# smart_tft.net
KiCad netlist of a schematic drawn in EAGLE
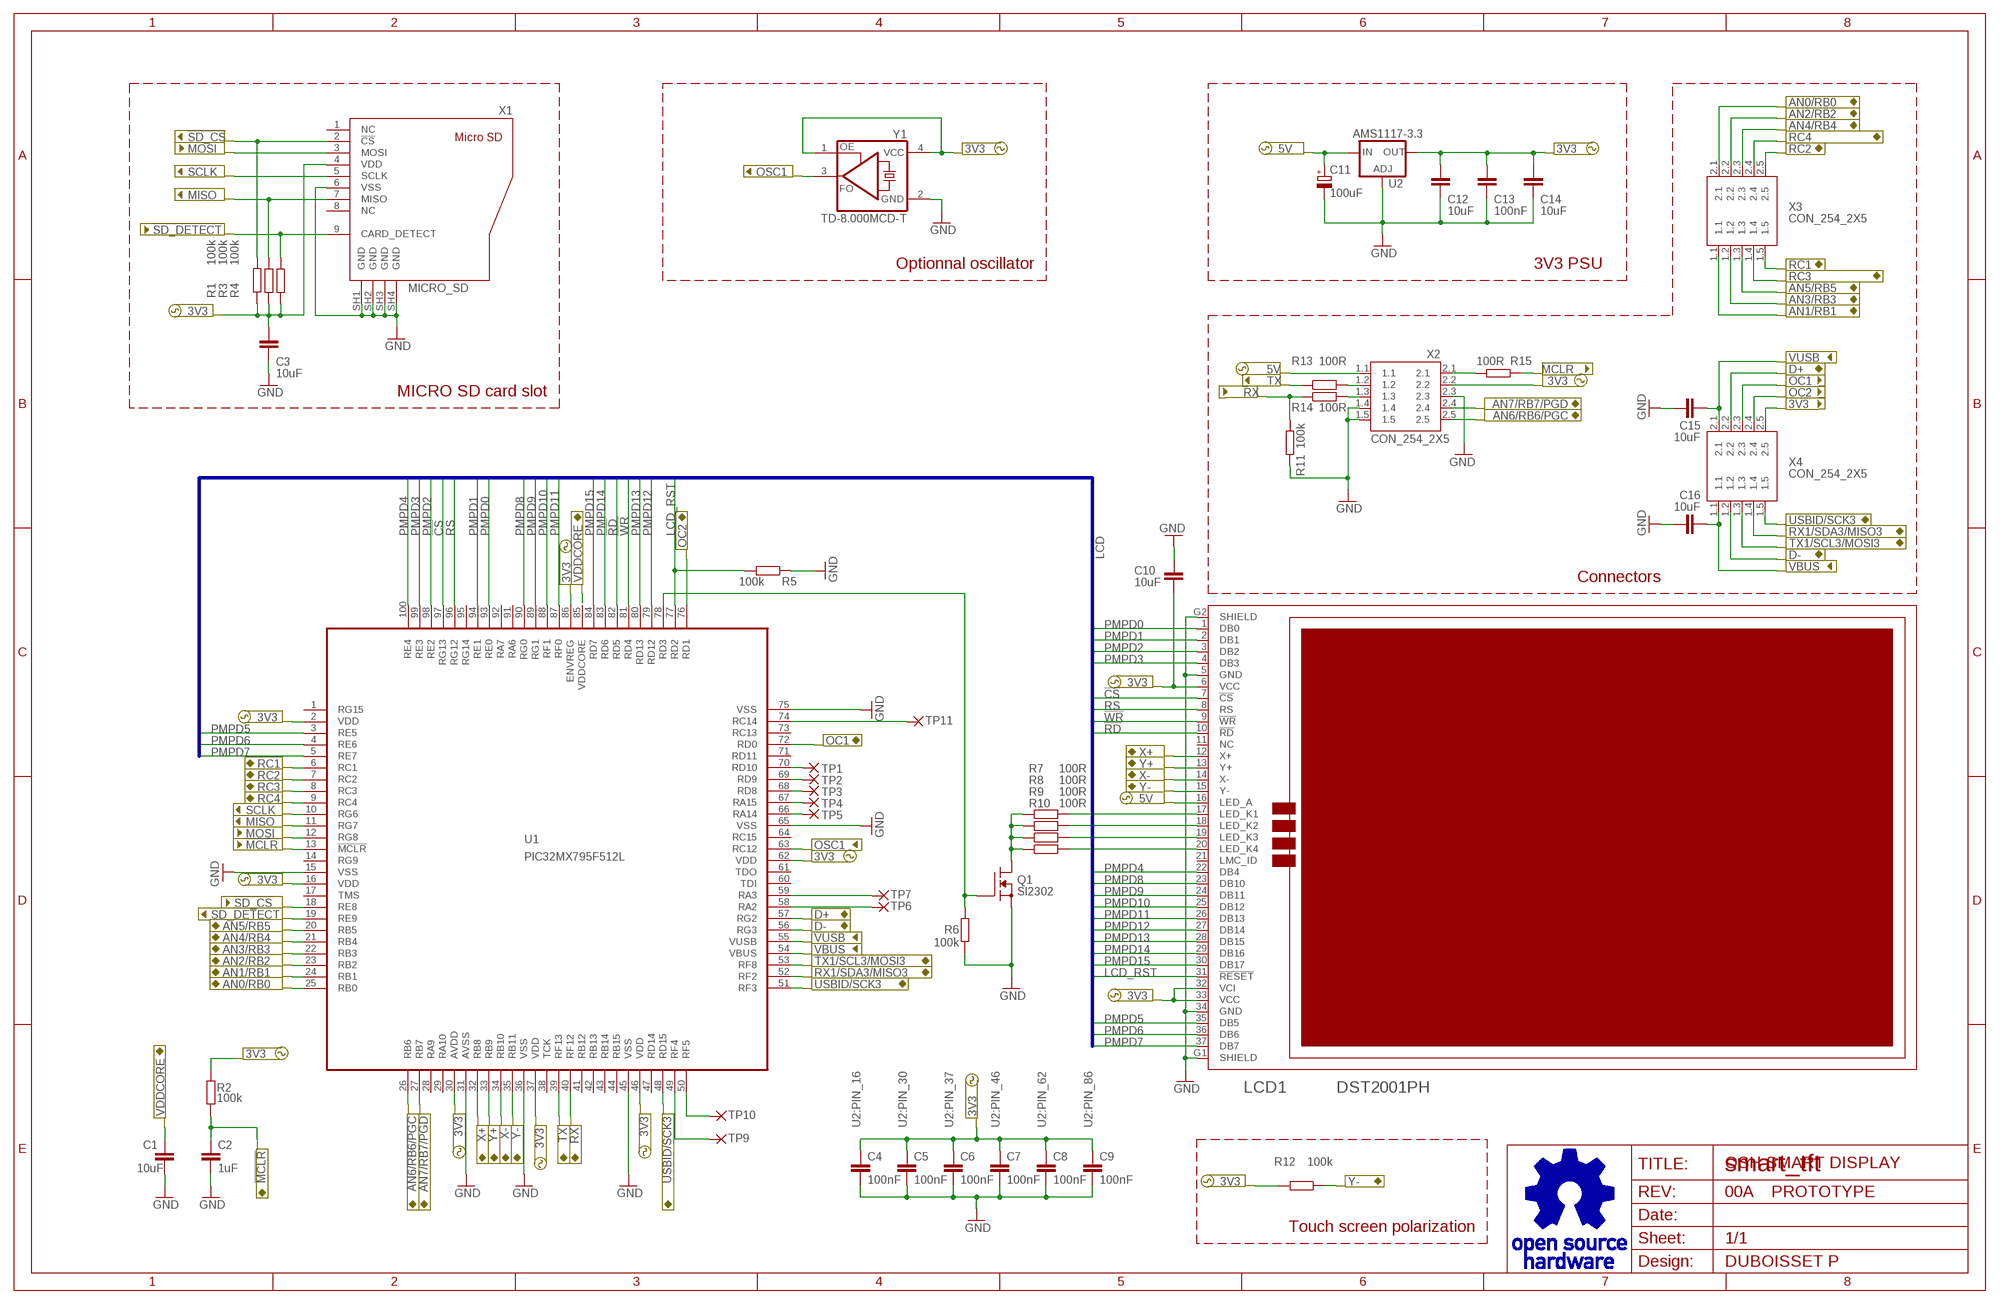
[diagram p0: schematic, sheet 1]

(export (version "E")
  (design (tool "Eeschema 10.0.6"))
  (components
    (comp (ref "C1")
      (value "10uF")
      (footprint "eagle-import:C0805")
      (libsource (lib "eagle-import") (part "C-EUC0805"))
    )
    (comp (ref "C2")
      (value "1uF")
      (footprint "eagle-import:C0603")
      (libsource (lib "eagle-import") (part "C-EUC0603"))
    )
    (comp (ref "C3")
      (value "10uF")
      (footprint "eagle-import:C0805")
      (libsource (lib "eagle-import") (part "C-EUC0805"))
    )
    (comp (ref "C4")
      (value "100nF")
      (footprint "eagle-import:C0603")
      (libsource (lib "eagle-import") (part "C-EUC0603"))
    )
    (comp (ref "C5")
      (value "100nF")
      (footprint "eagle-import:C0603")
      (libsource (lib "eagle-import") (part "C-EUC0603"))
    )
    (comp (ref "C6")
      (value "100nF")
      (footprint "eagle-import:C0603")
      (libsource (lib "eagle-import") (part "C-EUC0603"))
    )
    (comp (ref "C7")
      (value "100nF")
      (footprint "eagle-import:C0603")
      (libsource (lib "eagle-import") (part "C-EUC0603"))
    )
    (comp (ref "C8")
      (value "100nF")
      (footprint "eagle-import:C0603")
      (libsource (lib "eagle-import") (part "C-EUC0603"))
    )
    (comp (ref "C9")
      (value "100nF")
      (footprint "eagle-import:C0603")
      (libsource (lib "eagle-import") (part "C-EUC0603"))
    )
    (comp (ref "C10")
      (value "10uF")
      (footprint "eagle-import:C0805")
      (libsource (lib "eagle-import") (part "C-EUC0805"))
    )
    (comp (ref "C11")
      (value "100uF")
      (footprint "eagle-import:SMC_D")
      (libsource (lib "eagle-import") (part "CPOL-EUSMCD"))
    )
    (comp (ref "C12")
      (value "10uF")
      (footprint "eagle-import:C0805")
      (libsource (lib "eagle-import") (part "C-EUC0805"))
    )
    (comp (ref "C13")
      (value "100nF")
      (footprint "eagle-import:C0603")
      (libsource (lib "eagle-import") (part "C-EUC0603"))
    )
    (comp (ref "C14")
      (value "10uF")
      (footprint "eagle-import:C0805")
      (libsource (lib "eagle-import") (part "C-EUC0805"))
    )
    (comp (ref "C15")
      (value "10uF")
      (footprint "eagle-import:C0805")
      (libsource (lib "eagle-import") (part "C-EUC0805"))
    )
    (comp (ref "C16")
      (value "10uF")
      (footprint "eagle-import:C0805")
      (libsource (lib "eagle-import") (part "C-EUC0805"))
    )
    (comp (ref "LCD1")
      (value "DST2001PH")
      (footprint "eagle-import:DST2001PH")
      (libsource (lib "eagle-import") (part "DST2001PH"))
    )
    (comp (ref "Q1")
      (value "SI2302")
      (footprint "eagle-import:SOT23-BEC")
      (libsource (lib "eagle-import") (part "SI2302"))
    )
    (comp (ref "R1")
      (value "100k")
      (footprint "eagle-import:R0603")
      (libsource (lib "eagle-import") (part "R-EU_R0603"))
    )
    (comp (ref "R2")
      (value "100k")
      (footprint "eagle-import:R0603")
      (libsource (lib "eagle-import") (part "R-EU_R0603"))
    )
    (comp (ref "R3")
      (value "100k")
      (footprint "eagle-import:R0603")
      (libsource (lib "eagle-import") (part "R-EU_R0603"))
    )
    (comp (ref "R4")
      (value "100k")
      (footprint "eagle-import:R0603")
      (libsource (lib "eagle-import") (part "R-EU_R0603"))
    )
    (comp (ref "R5")
      (value "100k")
      (footprint "eagle-import:R0603")
      (libsource (lib "eagle-import") (part "R-EU_R0603"))
    )
    (comp (ref "R6")
      (value "100k")
      (footprint "eagle-import:R0603")
      (libsource (lib "eagle-import") (part "R-EU_R0603"))
    )
    (comp (ref "R7")
      (value "100R")
      (footprint "eagle-import:R0603")
      (libsource (lib "eagle-import") (part "R-EU_R0603"))
    )
    (comp (ref "R8")
      (value "100R")
      (footprint "eagle-import:R0603")
      (libsource (lib "eagle-import") (part "R-EU_R0603"))
    )
    (comp (ref "R9")
      (value "100R")
      (footprint "eagle-import:R0603")
      (libsource (lib "eagle-import") (part "R-EU_R0603"))
    )
    (comp (ref "R10")
      (value "100R")
      (footprint "eagle-import:R0603")
      (libsource (lib "eagle-import") (part "R-EU_R0603"))
    )
    (comp (ref "R11")
      (value "100k")
      (footprint "eagle-import:R0603")
      (libsource (lib "eagle-import") (part "R-EU_R0603"))
    )
    (comp (ref "R12")
      (value "100k")
      (footprint "eagle-import:R0603")
      (libsource (lib "eagle-import") (part "R-EU_R0603"))
    )
    (comp (ref "R13")
      (value "100R")
      (footprint "eagle-import:R0603")
      (libsource (lib "eagle-import") (part "R-EU_R0603"))
    )
    (comp (ref "R14")
      (value "100R")
      (footprint "eagle-import:R0603")
      (libsource (lib "eagle-import") (part "R-EU_R0603"))
    )
    (comp (ref "R15")
      (value "100R")
      (footprint "eagle-import:R0603")
      (libsource (lib "eagle-import") (part "R-EU_R0603"))
    )
    (comp (ref "TP1")
      (value "1.27R")
      (footprint "eagle-import:1.27R")
      (libsource (lib "eagle-import") (part "1.27R"))
    )
    (comp (ref "TP2")
      (value "1.27R")
      (footprint "eagle-import:1.27R")
      (libsource (lib "eagle-import") (part "1.27R"))
    )
    (comp (ref "TP3")
      (value "1.27R")
      (footprint "eagle-import:1.27R")
      (libsource (lib "eagle-import") (part "1.27R"))
    )
    (comp (ref "TP4")
      (value "1.27R")
      (footprint "eagle-import:1.27R")
      (libsource (lib "eagle-import") (part "1.27R"))
    )
    (comp (ref "TP5")
      (value "1.27R")
      (footprint "eagle-import:1.27R")
      (libsource (lib "eagle-import") (part "1.27R"))
    )
    (comp (ref "TP6")
      (value "1.27R")
      (footprint "eagle-import:1.27R")
      (libsource (lib "eagle-import") (part "1.27R"))
    )
    (comp (ref "TP7")
      (value "1.27R")
      (footprint "eagle-import:1.27R")
      (libsource (lib "eagle-import") (part "1.27R"))
    )
    (comp (ref "TP9")
      (value "1.27R")
      (footprint "eagle-import:1.27R")
      (libsource (lib "eagle-import") (part "1.27R"))
    )
    (comp (ref "TP10")
      (value "1.27R")
      (footprint "eagle-import:1.27R")
      (libsource (lib "eagle-import") (part "1.27R"))
    )
    (comp (ref "TP11")
      (value "1.27R")
      (footprint "eagle-import:1.27R")
      (libsource (lib "eagle-import") (part "1.27R"))
    )
    (comp (ref "U1")
      (value "PIC32MX795F512L")
      (footprint "eagle-import:TQFP100-14X14")
      (fields (field (name "MPN") "PIC24FJ256GB110-I/PF"))
      (libsource (lib "eagle-import") (part "PIC24FJ256GB110"))
    )
    (comp (ref "U2")
      (value "AMS1117-3.3")
      (footprint "eagle-import:SOT223")
      (libsource (lib "eagle-import") (part "LD117A?S33TR"))
    )
    (comp (ref "X1")
      (value "MICRO_SD")
      (footprint "eagle-import:SD_MICRO")
      (libsource (lib "eagle-import") (part "MICRO_SD"))
    )
    (comp (ref "X2")
      (value "CON_254_2X5")
      (footprint "eagle-import:2X5_CMS")
      (libsource (lib "eagle-import") (part "CON_254_2X5"))
    )
    (comp (ref "X3")
      (value "CON_254_2X5")
      (footprint "eagle-import:2X5_CMS")
      (libsource (lib "eagle-import") (part "CON_254_2X5"))
    )
    (comp (ref "X4")
      (value "CON_254_2X5")
      (footprint "eagle-import:2X5_CMS")
      (libsource (lib "eagle-import") (part "CON_254_2X5"))
    )
    (comp (ref "Y1")
      (value "TD-8.000MCD-T")
      (footprint "eagle-import:ASF")
      (libsource (lib "eagle-import") (part "ASF1"))
    )
  )
  (nets
    (net (code "2") (name "/3V3") (class "Default")
      (node (ref "C10") (pin "2") (pinfunction "2_2") (pintype "passive"))
      (node (ref "C12") (pin "1") (pinfunction "1_1") (pintype "passive"))
      (node (ref "C13") (pin "1") (pinfunction "1_1") (pintype "passive"))
      (node (ref "C14") (pin "1") (pinfunction "1_1") (pintype "passive"))
      (node (ref "C3") (pin "1") (pinfunction "1_1") (pintype "passive"))
      (node (ref "C4") (pin "1") (pinfunction "1_1") (pintype "passive"))
      (node (ref "C5") (pin "1") (pinfunction "1_1") (pintype "passive"))
      (node (ref "C6") (pin "1") (pinfunction "1_1") (pintype "passive"))
      (node (ref "C7") (pin "1") (pinfunction "1_1") (pintype "passive"))
      (node (ref "C8") (pin "1") (pinfunction "1_1") (pintype "passive"))
      (node (ref "C9") (pin "1") (pinfunction "1_1") (pintype "passive"))
      (node (ref "LCD1") (pin "32") (pinfunction "VCI_32") (pintype "bidirectional"))
      (node (ref "LCD1") (pin "33") (pinfunction "VCC_33") (pintype "bidirectional"))
      (node (ref "LCD1") (pin "6") (pinfunction "VCC_6") (pintype "bidirectional"))
      (node (ref "R1") (pin "1") (pinfunction "1_1") (pintype "passive"))
      (node (ref "R12") (pin "2") (pinfunction "2_2") (pintype "passive"))
      (node (ref "R2") (pin "2") (pinfunction "2_2") (pintype "passive"))
      (node (ref "R3") (pin "2") (pinfunction "2_2") (pintype "passive"))
      (node (ref "R4") (pin "2") (pinfunction "2_2") (pintype "passive"))
      (node (ref "U1") (pin "16") (pinfunction "VDD_16") (pintype "power_in"))
      (node (ref "U1") (pin "2") (pinfunction "VDD_2") (pintype "power_in"))
      (node (ref "U1") (pin "30") (pinfunction "AVDD_30") (pintype "power_in"))
      (node (ref "U1") (pin "37") (pinfunction "VDD_37") (pintype "power_in"))
      (node (ref "U1") (pin "46") (pinfunction "VDD_46") (pintype "power_in"))
      (node (ref "U1") (pin "62") (pinfunction "VDD_62") (pintype "power_in"))
      (node (ref "U1") (pin "86") (pinfunction "ENVREG_86") (pintype "passive"))
      (node (ref "U2") (pin "4") (pinfunction "OUT_4") (pintype "passive"))
      (node (ref "X1") (pin "4") (pinfunction "VDD_4") (pintype "bidirectional"))
      (node (ref "X2") (pin "2.2") (pinfunction "2.2_2.2") (pintype "bidirectional"))
      (node (ref "X4") (pin "2.5") (pinfunction "2.5_2.5") (pintype "bidirectional"))
      (node (ref "Y1") (pin "1") (pinfunction "OE_1") (pintype "input"))
      (node (ref "Y1") (pin "4") (pinfunction "VCC_4") (pintype "power_in"))
    )
    (net (code "3") (name "/5V") (class "Default")
      (node (ref "C11") (pin "+") (pinfunction "+_+") (pintype "passive"))
      (node (ref "LCD1") (pin "16") (pinfunction "LED_A_16") (pintype "bidirectional"))
      (node (ref "U2") (pin "3") (pinfunction "IN_3") (pintype "input"))
      (node (ref "X2") (pin "1.1") (pinfunction "1.1_1.1") (pintype "bidirectional"))
    )
    (net (code "4") (name "/AN0{slash}RB0") (class "Default")
      (node (ref "U1") (pin "25") (pinfunction "RB0_25") (pintype "bidirectional"))
      (node (ref "X3") (pin "2.1") (pinfunction "2.1_2.1") (pintype "bidirectional"))
    )
    (net (code "5") (name "/AN1{slash}RB1") (class "Default")
      (node (ref "U1") (pin "24") (pinfunction "RB1_24") (pintype "bidirectional"))
      (node (ref "X3") (pin "1.1") (pinfunction "1.1_1.1") (pintype "bidirectional"))
    )
    (net (code "6") (name "/AN2{slash}RB2") (class "Default")
      (node (ref "U1") (pin "23") (pinfunction "RB2_23") (pintype "bidirectional"))
      (node (ref "X3") (pin "2.2") (pinfunction "2.2_2.2") (pintype "bidirectional"))
    )
    (net (code "7") (name "/AN3{slash}RB3") (class "Default")
      (node (ref "U1") (pin "22") (pinfunction "RB3_22") (pintype "bidirectional"))
      (node (ref "X3") (pin "1.2") (pinfunction "1.2_1.2") (pintype "bidirectional"))
    )
    (net (code "8") (name "/AN4{slash}RB4") (class "Default")
      (node (ref "U1") (pin "21") (pinfunction "RB4_21") (pintype "bidirectional"))
      (node (ref "X3") (pin "2.3") (pinfunction "2.3_2.3") (pintype "bidirectional"))
    )
    (net (code "9") (name "/AN5{slash}RB5") (class "Default")
      (node (ref "U1") (pin "20") (pinfunction "RB5_20") (pintype "bidirectional"))
      (node (ref "X3") (pin "1.3") (pinfunction "1.3_1.3") (pintype "bidirectional"))
    )
    (net (code "10") (name "/AN6{slash}RB6{slash}PGC") (class "Default")
      (node (ref "U1") (pin "26") (pinfunction "RB6_26") (pintype "bidirectional"))
      (node (ref "X2") (pin "2.5") (pinfunction "2.5_2.5") (pintype "bidirectional"))
    )
    (net (code "11") (name "/AN7{slash}RB7{slash}PGD") (class "Default")
      (node (ref "U1") (pin "27") (pinfunction "RB7_27") (pintype "bidirectional"))
      (node (ref "X2") (pin "2.4") (pinfunction "2.4_2.4") (pintype "bidirectional"))
    )
    (net (code "12") (name "/D+") (class "Default")
      (node (ref "U1") (pin "57") (pinfunction "RG2_57") (pintype "bidirectional"))
      (node (ref "X4") (pin "2.2") (pinfunction "2.2_2.2") (pintype "bidirectional"))
    )
    (net (code "13") (name "/D-") (class "Default")
      (node (ref "U1") (pin "56") (pinfunction "RG3_56") (pintype "bidirectional"))
      (node (ref "X4") (pin "1.2") (pinfunction "1.2_1.2") (pintype "bidirectional"))
    )
    (net (code "14") (name "/LCD_RST") (class "Default")
      (node (ref "LCD1") (pin "31") (pinfunction "~{RESET}_31") (pintype "bidirectional"))
      (node (ref "R5") (pin "2") (pinfunction "2_2") (pintype "passive"))
      (node (ref "U1") (pin "77") (pinfunction "RD2_77") (pintype "bidirectional"))
    )
    (net (code "15") (name "/MISO") (class "Default")
      (node (ref "R3") (pin "1") (pinfunction "1_1") (pintype "passive"))
      (node (ref "U1") (pin "11") (pinfunction "RG7_11") (pintype "bidirectional"))
      (node (ref "X1") (pin "7") (pinfunction "MISO_7") (pintype "bidirectional"))
    )
    (net (code "16") (name "/MOSI") (class "Default")
      (node (ref "U1") (pin "12") (pinfunction "RG8_12") (pintype "bidirectional"))
      (node (ref "X1") (pin "3") (pinfunction "MOSI_3") (pintype "bidirectional"))
    )
    (net (code "17") (name "/OC1") (class "Default")
      (node (ref "U1") (pin "72") (pinfunction "RD0_72") (pintype "bidirectional"))
      (node (ref "X4") (pin "2.3") (pinfunction "2.3_2.3") (pintype "bidirectional"))
    )
    (net (code "18") (name "/OC2") (class "Default")
      (node (ref "U1") (pin "76") (pinfunction "RD1_76") (pintype "bidirectional"))
      (node (ref "X4") (pin "2.4") (pinfunction "2.4_2.4") (pintype "bidirectional"))
    )
    (net (code "19") (name "/OSC1") (class "Default")
      (node (ref "U1") (pin "63") (pinfunction "RC12_63") (pintype "bidirectional"))
      (node (ref "Y1") (pin "3") (pinfunction "FO_3") (pintype "output"))
    )
    (net (code "20") (name "/PMPD0") (class "Default")
      (node (ref "LCD1") (pin "1") (pinfunction "DB0_1") (pintype "bidirectional"))
      (node (ref "U1") (pin "93") (pinfunction "RE0_93") (pintype "bidirectional"))
    )
    (net (code "21") (name "/PMPD1") (class "Default")
      (node (ref "LCD1") (pin "2") (pinfunction "DB1_2") (pintype "bidirectional"))
      (node (ref "U1") (pin "94") (pinfunction "RE1_94") (pintype "bidirectional"))
    )
    (net (code "22") (name "/PMPD2") (class "Default")
      (node (ref "LCD1") (pin "3") (pinfunction "DB2_3") (pintype "bidirectional"))
      (node (ref "U1") (pin "98") (pinfunction "RE2_98") (pintype "bidirectional"))
    )
    (net (code "23") (name "/PMPD3") (class "Default")
      (node (ref "LCD1") (pin "4") (pinfunction "DB3_4") (pintype "bidirectional"))
      (node (ref "U1") (pin "99") (pinfunction "RE3_99") (pintype "bidirectional"))
    )
    (net (code "24") (name "/PMPD4") (class "Default")
      (node (ref "LCD1") (pin "22") (pinfunction "DB4_22") (pintype "bidirectional"))
      (node (ref "U1") (pin "100") (pinfunction "RE4_100") (pintype "bidirectional"))
    )
    (net (code "25") (name "/PMPD5") (class "Default")
      (node (ref "LCD1") (pin "35") (pinfunction "DB5_35") (pintype "bidirectional"))
      (node (ref "U1") (pin "3") (pinfunction "RE5_3") (pintype "bidirectional"))
    )
    (net (code "26") (name "/PMPD6") (class "Default")
      (node (ref "LCD1") (pin "36") (pinfunction "DB6_36") (pintype "bidirectional"))
      (node (ref "U1") (pin "4") (pinfunction "RE6_4") (pintype "bidirectional"))
    )
    (net (code "27") (name "/PMPD7") (class "Default")
      (node (ref "LCD1") (pin "37") (pinfunction "DB7_37") (pintype "bidirectional"))
      (node (ref "U1") (pin "5") (pinfunction "RE7_5") (pintype "bidirectional"))
    )
    (net (code "28") (name "/PMPD8") (class "Default")
      (node (ref "LCD1") (pin "23") (pinfunction "DB10_23") (pintype "bidirectional"))
      (node (ref "U1") (pin "90") (pinfunction "RG0_90") (pintype "bidirectional"))
    )
    (net (code "29") (name "/PMPD9") (class "Default")
      (node (ref "LCD1") (pin "24") (pinfunction "DB11_24") (pintype "bidirectional"))
      (node (ref "U1") (pin "89") (pinfunction "RG1_89") (pintype "bidirectional"))
    )
    (net (code "30") (name "/PMPD10") (class "Default")
      (node (ref "LCD1") (pin "25") (pinfunction "DB12_25") (pintype "bidirectional"))
      (node (ref "U1") (pin "88") (pinfunction "RF1_88") (pintype "bidirectional"))
    )
    (net (code "31") (name "/PMPD11") (class "Default")
      (node (ref "LCD1") (pin "26") (pinfunction "DB13_26") (pintype "bidirectional"))
      (node (ref "U1") (pin "87") (pinfunction "RF0_87") (pintype "bidirectional"))
    )
    (net (code "32") (name "/PMPD12") (class "Default")
      (node (ref "LCD1") (pin "27") (pinfunction "DB14_27") (pintype "bidirectional"))
      (node (ref "U1") (pin "79") (pinfunction "RD12_79") (pintype "bidirectional"))
    )
    (net (code "33") (name "/PMPD13") (class "Default")
      (node (ref "LCD1") (pin "28") (pinfunction "DB15_28") (pintype "bidirectional"))
      (node (ref "U1") (pin "80") (pinfunction "RD13_80") (pintype "bidirectional"))
    )
    (net (code "34") (name "/PMPD14") (class "Default")
      (node (ref "LCD1") (pin "29") (pinfunction "DB16_29") (pintype "bidirectional"))
      (node (ref "U1") (pin "83") (pinfunction "RD6_83") (pintype "bidirectional"))
    )
    (net (code "35") (name "/PMPD15") (class "Default")
      (node (ref "LCD1") (pin "30") (pinfunction "DB17_30") (pintype "bidirectional"))
      (node (ref "U1") (pin "84") (pinfunction "RD7_84") (pintype "bidirectional"))
    )
    (net (code "36") (name "/RC1") (class "Default")
      (node (ref "U1") (pin "6") (pinfunction "RC1_6") (pintype "bidirectional"))
      (node (ref "X3") (pin "1.5") (pinfunction "1.5_1.5") (pintype "bidirectional"))
    )
    (net (code "37") (name "/RC2") (class "Default")
      (node (ref "U1") (pin "7") (pinfunction "RC2_7") (pintype "bidirectional"))
      (node (ref "X3") (pin "2.5") (pinfunction "2.5_2.5") (pintype "bidirectional"))
    )
    (net (code "38") (name "/RC3") (class "Default")
      (node (ref "U1") (pin "8") (pinfunction "RC3_8") (pintype "bidirectional"))
      (node (ref "X3") (pin "1.4") (pinfunction "1.4_1.4") (pintype "bidirectional"))
    )
    (net (code "39") (name "/RC4") (class "Default")
      (node (ref "U1") (pin "9") (pinfunction "RC4_9") (pintype "bidirectional"))
      (node (ref "X3") (pin "2.4") (pinfunction "2.4_2.4") (pintype "bidirectional"))
    )
    (net (code "40") (name "/RS") (class "Default")
      (node (ref "LCD1") (pin "8") (pinfunction "RS_8") (pintype "bidirectional"))
      (node (ref "U1") (pin "96") (pinfunction "RG12_96") (pintype "bidirectional"))
    )
    (net (code "41") (name "/RX") (class "Default")
      (node (ref "R11") (pin "2") (pinfunction "2_2") (pintype "passive"))
      (node (ref "R14") (pin "1") (pinfunction "1_1") (pintype "passive"))
      (node (ref "U1") (pin "40") (pinfunction "RF12_40") (pintype "bidirectional"))
    )
    (net (code "42") (name "/RX1{slash}SDA3{slash}MISO3") (class "Default")
      (node (ref "U1") (pin "52") (pinfunction "RF2_52") (pintype "bidirectional"))
      (node (ref "X4") (pin "1.4") (pinfunction "1.4_1.4") (pintype "bidirectional"))
    )
    (net (code "43") (name "/SCLK") (class "Default")
      (node (ref "U1") (pin "10") (pinfunction "RG6_10") (pintype "bidirectional"))
      (node (ref "X1") (pin "5") (pinfunction "SCLK_5") (pintype "bidirectional"))
    )
    (net (code "44") (name "/TX") (class "Default")
      (node (ref "R13") (pin "1") (pinfunction "1_1") (pintype "passive"))
      (node (ref "U1") (pin "39") (pinfunction "RF13_39") (pintype "bidirectional"))
    )
    (net (code "45") (name "/TX1{slash}SCL3{slash}MOSI3") (class "Default")
      (node (ref "U1") (pin "53") (pinfunction "RF8_53") (pintype "bidirectional"))
      (node (ref "X4") (pin "1.3") (pinfunction "1.3_1.3") (pintype "bidirectional"))
    )
    (net (code "46") (name "/USBID{slash}SCK3") (class "Default")
      (node (ref "U1") (pin "48") (pinfunction "RD15_48") (pintype "bidirectional"))
      (node (ref "U1") (pin "51") (pinfunction "RF3_51") (pintype "bidirectional"))
      (node (ref "X4") (pin "1.5") (pinfunction "1.5_1.5") (pintype "bidirectional"))
    )
    (net (code "47") (name "/VBUS") (class "Default")
      (node (ref "C16") (pin "1") (pinfunction "1_1") (pintype "passive"))
      (node (ref "U1") (pin "54") (pinfunction "VBUS_54") (pintype "passive"))
      (node (ref "X4") (pin "1.1") (pinfunction "1.1_1.1") (pintype "bidirectional"))
    )
    (net (code "48") (name "/VDDCORE") (class "Default")
      (node (ref "C1") (pin "2") (pinfunction "2_2") (pintype "passive"))
      (node (ref "U1") (pin "85") (pinfunction "VDDCORE_85") (pintype "power_in"))
    )
    (net (code "49") (name "/VUSB") (class "Default")
      (node (ref "C15") (pin "1") (pinfunction "1_1") (pintype "passive"))
      (node (ref "U1") (pin "55") (pinfunction "VUSB_55") (pintype "passive"))
      (node (ref "X4") (pin "2.1") (pinfunction "2.1_2.1") (pintype "bidirectional"))
    )
    (net (code "50") (name "/X+") (class "Default")
      (node (ref "LCD1") (pin "12") (pinfunction "X+_12") (pintype "bidirectional"))
      (node (ref "U1") (pin "32") (pinfunction "RB8_32") (pintype "bidirectional"))
    )
    (net (code "51") (name "/X-") (class "Default")
      (node (ref "LCD1") (pin "14") (pinfunction "X-_14") (pintype "bidirectional"))
      (node (ref "U1") (pin "34") (pinfunction "RB10_34") (pintype "bidirectional"))
    )
    (net (code "52") (name "/Y+") (class "Default")
      (node (ref "LCD1") (pin "13") (pinfunction "Y+_13") (pintype "bidirectional"))
      (node (ref "U1") (pin "33") (pinfunction "RB9_33") (pintype "bidirectional"))
    )
    (net (code "53") (name "/Y-") (class "Default")
      (node (ref "LCD1") (pin "15") (pinfunction "Y-_15") (pintype "bidirectional"))
      (node (ref "R12") (pin "1") (pinfunction "1_1") (pintype "passive"))
      (node (ref "U1") (pin "35") (pinfunction "RB11_35") (pintype "bidirectional"))
    )
    (net (code "55") (name "/~{CS}") (class "Default")
      (node (ref "LCD1") (pin "7") (pinfunction "~{CS}_7") (pintype "bidirectional"))
      (node (ref "U1") (pin "97") (pinfunction "RG13_97") (pintype "bidirectional"))
    )
    (net (code "56") (name "/~{MCLR}") (class "Default")
      (node (ref "C2") (pin "1") (pinfunction "1_1") (pintype "passive"))
      (node (ref "R15") (pin "1") (pinfunction "1_1") (pintype "passive"))
      (node (ref "R2") (pin "1") (pinfunction "1_1") (pintype "passive"))
      (node (ref "U1") (pin "13") (pinfunction "~{MCLR}_13") (pintype "bidirectional"))
    )
    (net (code "57") (name "/~{RD}") (class "Default")
      (node (ref "LCD1") (pin "10") (pinfunction "~{RD}_10") (pintype "bidirectional"))
      (node (ref "U1") (pin "82") (pinfunction "RD5_82") (pintype "bidirectional"))
    )
    (net (code "58") (name "/~{SD_CS}") (class "Default")
      (node (ref "R1") (pin "2") (pinfunction "2_2") (pintype "passive"))
      (node (ref "U1") (pin "18") (pinfunction "RE8_18") (pintype "bidirectional"))
      (node (ref "X1") (pin "2") (pinfunction "~{CS}_2") (pintype "bidirectional"))
    )
    (net (code "59") (name "/~{SD_DETECT}") (class "Default")
      (node (ref "R4") (pin "1") (pinfunction "1_1") (pintype "passive"))
      (node (ref "U1") (pin "19") (pinfunction "RE9_19") (pintype "bidirectional"))
      (node (ref "X1") (pin "9") (pinfunction "CARD_DETECT_9") (pintype "bidirectional"))
    )
    (net (code "60") (name "/~{WR}") (class "Default")
      (node (ref "LCD1") (pin "9") (pinfunction "~{WR}_9") (pintype "bidirectional"))
      (node (ref "U1") (pin "81") (pinfunction "RD4_81") (pintype "bidirectional"))
    )
    (net (code "61") (name "GND") (class "Default")
      (node (ref "C1") (pin "1") (pinfunction "1_1") (pintype "passive"))
      (node (ref "C10") (pin "1") (pinfunction "1_1") (pintype "passive"))
      (node (ref "C11") (pin "-") (pinfunction "-_-") (pintype "passive"))
      (node (ref "C12") (pin "2") (pinfunction "2_2") (pintype "passive"))
      (node (ref "C13") (pin "2") (pinfunction "2_2") (pintype "passive"))
      (node (ref "C14") (pin "2") (pinfunction "2_2") (pintype "passive"))
      (node (ref "C15") (pin "2") (pinfunction "2_2") (pintype "passive"))
      (node (ref "C16") (pin "2") (pinfunction "2_2") (pintype "passive"))
      (node (ref "C2") (pin "2") (pinfunction "2_2") (pintype "passive"))
      (node (ref "C3") (pin "2") (pinfunction "2_2") (pintype "passive"))
      (node (ref "C4") (pin "2") (pinfunction "2_2") (pintype "passive"))
      (node (ref "C5") (pin "2") (pinfunction "2_2") (pintype "passive"))
      (node (ref "C6") (pin "2") (pinfunction "2_2") (pintype "passive"))
      (node (ref "C7") (pin "2") (pinfunction "2_2") (pintype "passive"))
      (node (ref "C8") (pin "2") (pinfunction "2_2") (pintype "passive"))
      (node (ref "C9") (pin "2") (pinfunction "2_2") (pintype "passive"))
      (node (ref "LCD1") (pin "34") (pinfunction "GND_34") (pintype "bidirectional"))
      (node (ref "LCD1") (pin "5") (pinfunction "GND_5") (pintype "bidirectional"))
      (node (ref "LCD1") (pin "G1") (pinfunction "SHIELD_G1") (pintype "bidirectional"))
      (node (ref "LCD1") (pin "G2") (pinfunction "SHIELD_G2") (pintype "bidirectional"))
      (node (ref "Q1") (pin "E") (pinfunction "S_E") (pintype "passive"))
      (node (ref "R11") (pin "1") (pinfunction "1_1") (pintype "passive"))
      (node (ref "R5") (pin "1") (pinfunction "1_1") (pintype "passive"))
      (node (ref "R6") (pin "1") (pinfunction "1_1") (pintype "passive"))
      (node (ref "U1") (pin "15") (pinfunction "VSS_15") (pintype "power_in"))
      (node (ref "U1") (pin "31") (pinfunction "AVSS_31") (pintype "power_in"))
      (node (ref "U1") (pin "36") (pinfunction "VSS_36") (pintype "power_in"))
      (node (ref "U1") (pin "45") (pinfunction "VSS_45") (pintype "power_in"))
      (node (ref "U1") (pin "65") (pinfunction "VSS_65") (pintype "power_in"))
      (node (ref "U1") (pin "75") (pinfunction "VSS_75") (pintype "power_in"))
      (node (ref "U2") (pin "1") (pinfunction "ADJ_1") (pintype "input"))
      (node (ref "X1") (pin "6") (pinfunction "VSS_6") (pintype "bidirectional"))
      (node (ref "X1") (pin "SH1") (pinfunction "GND_SH1") (pintype "bidirectional"))
      (node (ref "X1") (pin "SH2") (pinfunction "GND_SH2") (pintype "bidirectional"))
      (node (ref "X1") (pin "SH3") (pinfunction "GND_SH3") (pintype "bidirectional"))
      (node (ref "X1") (pin "SH4") (pinfunction "GND_SH4") (pintype "bidirectional"))
      (node (ref "X2") (pin "1.4") (pinfunction "1.4_1.4") (pintype "bidirectional"))
      (node (ref "X2") (pin "1.5") (pinfunction "1.5_1.5") (pintype "bidirectional"))
      (node (ref "X2") (pin "2.3") (pinfunction "2.3_2.3") (pintype "bidirectional"))
      (node (ref "Y1") (pin "2") (pinfunction "GND_2") (pintype "power_in"))
    )
    (net (code "62") (name "Net-(LCD1-LED_K1)") (class "Default")
      (node (ref "LCD1") (pin "17") (pinfunction "LED_K1_17") (pintype "bidirectional"))
      (node (ref "R7") (pin "2") (pinfunction "2_2") (pintype "passive"))
    )
    (net (code "63") (name "Net-(LCD1-LED_K2)") (class "Default")
      (node (ref "LCD1") (pin "18") (pinfunction "LED_K2_18") (pintype "bidirectional"))
      (node (ref "R8") (pin "2") (pinfunction "2_2") (pintype "passive"))
    )
    (net (code "64") (name "Net-(LCD1-LED_K3)") (class "Default")
      (node (ref "LCD1") (pin "19") (pinfunction "LED_K3_19") (pintype "bidirectional"))
      (node (ref "R9") (pin "2") (pinfunction "2_2") (pintype "passive"))
    )
    (net (code "65") (name "Net-(LCD1-LED_K4)") (class "Default")
      (node (ref "LCD1") (pin "20") (pinfunction "LED_K4_20") (pintype "bidirectional"))
      (node (ref "R10") (pin "2") (pinfunction "2_2") (pintype "passive"))
    )
    (net (code "66") (name "Net-(Q1-D)") (class "Default")
      (node (ref "Q1") (pin "C") (pinfunction "D_C") (pintype "passive"))
      (node (ref "R10") (pin "1") (pinfunction "1_1") (pintype "passive"))
      (node (ref "R7") (pin "1") (pinfunction "1_1") (pintype "passive"))
      (node (ref "R8") (pin "1") (pinfunction "1_1") (pintype "passive"))
      (node (ref "R9") (pin "1") (pinfunction "1_1") (pintype "passive"))
    )
    (net (code "67") (name "Net-(Q1-G)") (class "Default")
      (node (ref "Q1") (pin "B") (pinfunction "G_B") (pintype "passive"))
      (node (ref "R6") (pin "2") (pinfunction "2_2") (pintype "passive"))
      (node (ref "U1") (pin "78") (pinfunction "RD3_78") (pintype "bidirectional"))
    )
    (net (code "68") (name "Net-(R13-Pad2)") (class "Default")
      (node (ref "R13") (pin "2") (pinfunction "2_2") (pintype "passive"))
      (node (ref "X2") (pin "1.2") (pinfunction "1.2_1.2") (pintype "bidirectional"))
    )
    (net (code "69") (name "Net-(R14-Pad2)") (class "Default")
      (node (ref "R14") (pin "2") (pinfunction "2_2") (pintype "passive"))
      (node (ref "X2") (pin "1.3") (pinfunction "1.3_1.3") (pintype "bidirectional"))
    )
    (net (code "70") (name "Net-(R15-Pad2)") (class "Default")
      (node (ref "R15") (pin "2") (pinfunction "2_2") (pintype "passive"))
      (node (ref "X2") (pin "2.1") (pinfunction "2.1_2.1") (pintype "bidirectional"))
    )
    (net (code "71") (name "Net-(TP1-P)") (class "Default")
      (node (ref "TP1") (pin "P$1") (pinfunction "P_P$1") (pintype "passive"))
      (node (ref "U1") (pin "70") (pinfunction "RD10_70") (pintype "bidirectional"))
    )
    (net (code "72") (name "Net-(TP2-P)") (class "Default")
      (node (ref "TP2") (pin "P$1") (pinfunction "P_P$1") (pintype "passive"))
      (node (ref "U1") (pin "69") (pinfunction "RD9_69") (pintype "bidirectional"))
    )
    (net (code "73") (name "Net-(TP3-P)") (class "Default")
      (node (ref "TP3") (pin "P$1") (pinfunction "P_P$1") (pintype "passive"))
      (node (ref "U1") (pin "68") (pinfunction "RD8_68") (pintype "bidirectional"))
    )
    (net (code "74") (name "Net-(TP4-P)") (class "Default")
      (node (ref "TP4") (pin "P$1") (pinfunction "P_P$1") (pintype "passive"))
      (node (ref "U1") (pin "67") (pinfunction "RA15_67") (pintype "bidirectional"))
    )
    (net (code "75") (name "Net-(TP5-P)") (class "Default")
      (node (ref "TP5") (pin "P$1") (pinfunction "P_P$1") (pintype "passive"))
      (node (ref "U1") (pin "66") (pinfunction "RA14_66") (pintype "bidirectional"))
    )
    (net (code "76") (name "Net-(TP6-P)") (class "Default")
      (node (ref "TP6") (pin "P$1") (pinfunction "P_P$1") (pintype "passive"))
      (node (ref "U1") (pin "58") (pinfunction "RA2_58") (pintype "bidirectional"))
    )
    (net (code "77") (name "Net-(TP7-P)") (class "Default")
      (node (ref "TP7") (pin "P$1") (pinfunction "P_P$1") (pintype "passive"))
      (node (ref "U1") (pin "59") (pinfunction "RA3_59") (pintype "bidirectional"))
    )
    (net (code "78") (name "Net-(TP9-P)") (class "Default")
      (node (ref "TP9") (pin "P$1") (pinfunction "P_P$1") (pintype "passive"))
      (node (ref "U1") (pin "49") (pinfunction "RF4_49") (pintype "bidirectional"))
    )
    (net (code "79") (name "Net-(TP10-P)") (class "Default")
      (node (ref "TP10") (pin "P$1") (pinfunction "P_P$1") (pintype "passive"))
      (node (ref "U1") (pin "50") (pinfunction "RF5_50") (pintype "bidirectional"))
    )
    (net (code "80") (name "Net-(TP11-P)") (class "Default")
      (node (ref "TP11") (pin "P$1") (pinfunction "P_P$1") (pintype "passive"))
      (node (ref "U1") (pin "74") (pinfunction "RC14_74") (pintype "bidirectional"))
    )
    (net (code "81") (name "unconnected-(LCD1-LMC_ID-Pad21)") (class "Default")
      (node (ref "LCD1") (pin "21") (pinfunction "LMC_ID_21") (pintype "bidirectional"))
    )
    (net (code "82") (name "unconnected-(LCD1-NC-Pad11)") (class "Default")
      (node (ref "LCD1") (pin "11") (pinfunction "NC_11") (pintype "bidirectional"))
    )
    (net (code "83") (name "unconnected-(U1-RA6-Pad91)") (class "Default")
      (node (ref "U1") (pin "91") (pinfunction "RA6_91") (pintype "bidirectional"))
    )
    (net (code "84") (name "unconnected-(U1-RA7-Pad92)") (class "Default")
      (node (ref "U1") (pin "92") (pinfunction "RA7_92") (pintype "bidirectional"))
    )
    (net (code "85") (name "unconnected-(U1-RA9-Pad28)") (class "Default")
      (node (ref "U1") (pin "28") (pinfunction "RA9_28") (pintype "bidirectional"))
    )
    (net (code "86") (name "unconnected-(U1-RA10-Pad29)") (class "Default")
      (node (ref "U1") (pin "29") (pinfunction "RA10_29") (pintype "bidirectional"))
    )
    (net (code "87") (name "unconnected-(U1-RB12-Pad41)") (class "Default")
      (node (ref "U1") (pin "41") (pinfunction "RB12_41") (pintype "bidirectional"))
    )
    (net (code "88") (name "unconnected-(U1-RB13-Pad42)") (class "Default")
      (node (ref "U1") (pin "42") (pinfunction "RB13_42") (pintype "bidirectional"))
    )
    (net (code "89") (name "unconnected-(U1-RB14-Pad43)") (class "Default")
      (node (ref "U1") (pin "43") (pinfunction "RB14_43") (pintype "bidirectional"))
    )
    (net (code "90") (name "unconnected-(U1-RB15-Pad44)") (class "Default")
      (node (ref "U1") (pin "44") (pinfunction "RB15_44") (pintype "bidirectional"))
    )
    (net (code "91") (name "unconnected-(U1-RC13-Pad73)") (class "Default")
      (node (ref "U1") (pin "73") (pinfunction "RC13_73") (pintype "bidirectional"))
    )
    (net (code "92") (name "unconnected-(U1-RC15-Pad64)") (class "Default")
      (node (ref "U1") (pin "64") (pinfunction "RC15_64") (pintype "bidirectional"))
    )
    (net (code "93") (name "unconnected-(U1-RD11-Pad71)") (class "Default")
      (node (ref "U1") (pin "71") (pinfunction "RD11_71") (pintype "bidirectional"))
    )
    (net (code "94") (name "unconnected-(U1-RD14-Pad47)") (class "Default")
      (node (ref "U1") (pin "47") (pinfunction "RD14_47") (pintype "bidirectional"))
    )
    (net (code "95") (name "unconnected-(U1-RG9-Pad14)") (class "Default")
      (node (ref "U1") (pin "14") (pinfunction "RG9_14") (pintype "bidirectional"))
    )
    (net (code "96") (name "unconnected-(U1-RG14-Pad95)") (class "Default")
      (node (ref "U1") (pin "95") (pinfunction "RG14_95") (pintype "bidirectional"))
    )
    (net (code "97") (name "unconnected-(U1-RG15-Pad1)") (class "Default")
      (node (ref "U1") (pin "1") (pinfunction "RG15_1") (pintype "bidirectional"))
    )
    (net (code "98") (name "unconnected-(U1-TCK-Pad38)") (class "Default")
      (node (ref "U1") (pin "38") (pinfunction "TCK_38") (pintype "input"))
    )
    (net (code "99") (name "unconnected-(U1-TDI-Pad60)") (class "Default")
      (node (ref "U1") (pin "60") (pinfunction "TDI_60") (pintype "input"))
    )
    (net (code "100") (name "unconnected-(U1-TDO-Pad61)") (class "Default")
      (node (ref "U1") (pin "61") (pinfunction "TDO_61") (pintype "output"))
    )
    (net (code "101") (name "unconnected-(U1-TMS-Pad17)") (class "Default")
      (node (ref "U1") (pin "17") (pinfunction "TMS_17") (pintype "input"))
    )
    (net (code "102") (name "unconnected-(X1-NC-Pad1)") (class "Default")
      (node (ref "X1") (pin "1") (pinfunction "NC_1") (pintype "bidirectional"))
    )
    (net (code "103") (name "unconnected-(X1-NC-Pad8)") (class "Default")
      (node (ref "X1") (pin "8") (pinfunction "NC_8") (pintype "bidirectional"))
    )
  )
)
